# 260115710xxxx-HW-2_0.net
KiCad netlist of a schematic drawn in Altium Designer
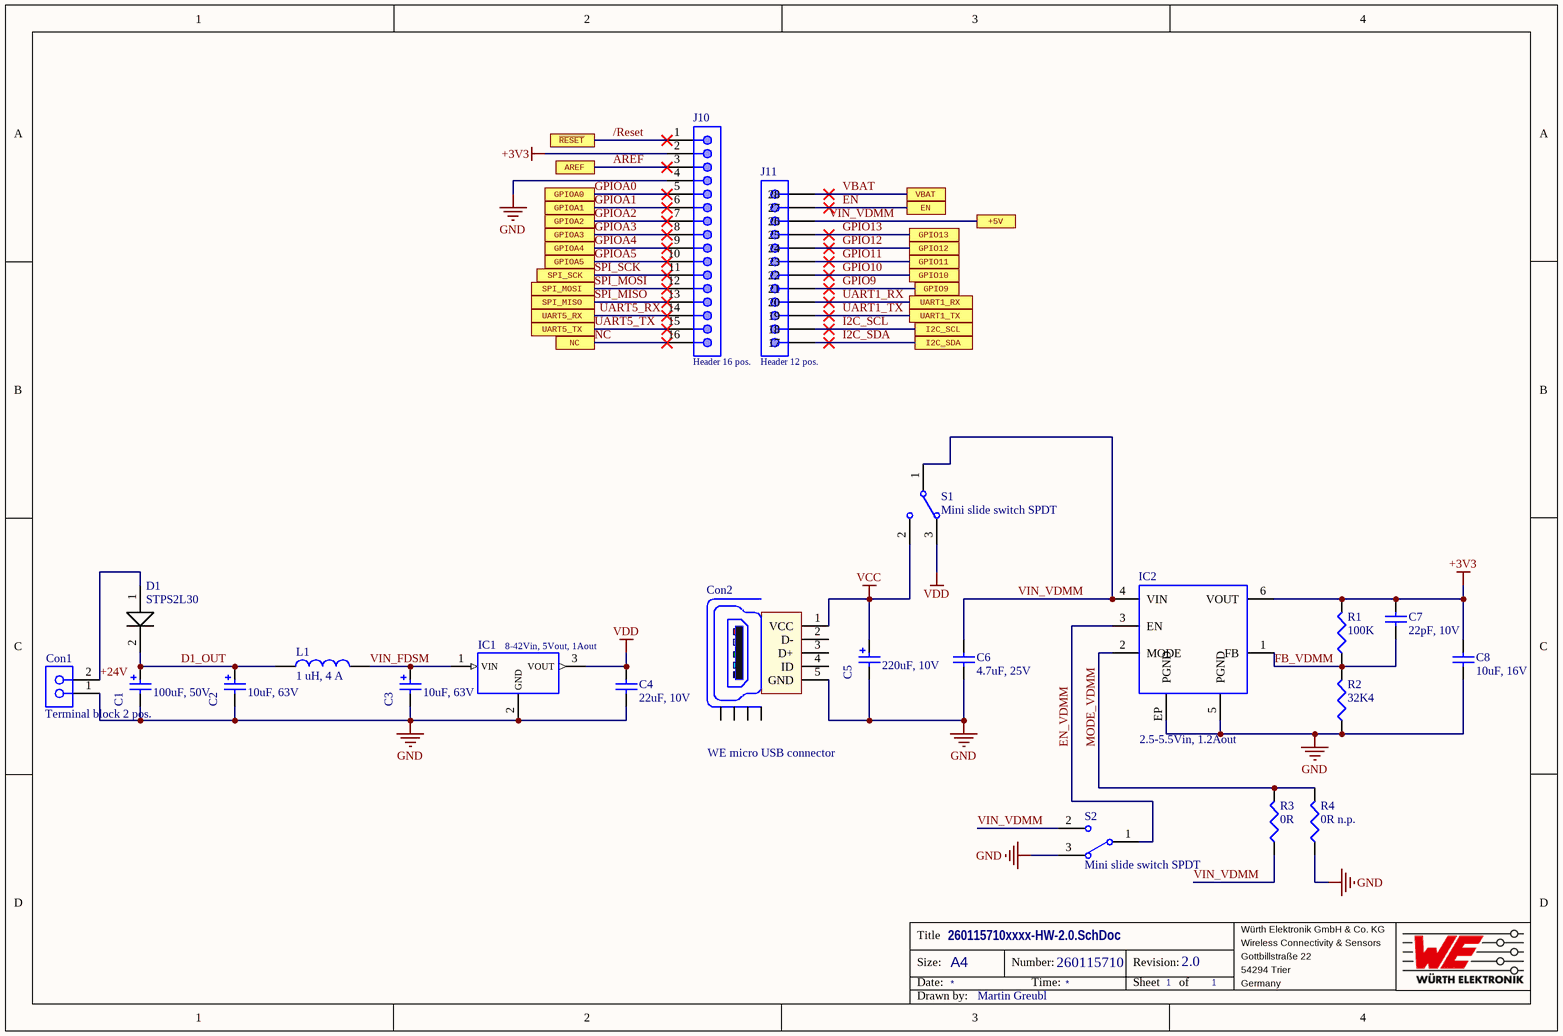
[diagram p0: 260115710xxxx-HW-2.0.SchDoc]

(export (version "E")
  (design (tool "Eeschema 10.0.6"))
  (components
    (comp (ref "C1")
      (value "100uF, 50V")
      (footprint "WCAP-ATG8_8x11.5")
      (description "WCAP-ATG8 THT Aluminum Electrolytic Capacitors, D8mm x L11.5mm, 100uF, +/-20%, 50VDC")
      (fields
        (field (name "PART NUMBER") "860010674014")
        (field (name "MANUFACTURER") "Würth Elektronik eiSos")
        (field (name "PUBLISHER") "Wurth Elektronik")
      )
      (libsource (lib "860010672001_Altium_WCAP-ATG8_rev19a") (part "860010674014"))
    )
    (comp (ref "C2")
      (value "10uF, 63V")
      (footprint "WCAP-PSHP_8x8.7mm")
      (description "WCAP-PSHP Aluminum Polymer Capacitors, size 8x8.7mm, 10uF, +/-20%, 63VDC")
      (fields
        (field (name "PART NUMBER") "875115852001")
        (field (name "MANUFACTURER") "Würth Elektronik eiSos")
        (field (name "PUBLISHER") "Wurth Elektronik")
      )
      (libsource (lib "875115852001_Altium_WCAP-PSHP_rev19a") (part "875115852001"))
    )
    (comp (ref "C3")
      (value "10uF, 63V")
      (footprint "WCAP-PSHP_8x8.7mm")
      (description "WCAP-PSHP Aluminum Polymer Capacitors, size 8x8.7mm, 10uF, +/-20%, 63VDC")
      (fields
        (field (name "PART NUMBER") "875115852001")
        (field (name "MANUFACTURER") "Würth Elektronik eiSos")
        (field (name "PUBLISHER") "Wurth Elektronik")
      )
      (libsource (lib "875115852001_Altium_WCAP-PSHP_rev19a") (part "875115852001"))
    )
    (comp (ref "C4")
      (value "22uF, 10V")
      (footprint "WCAP-CSGP_0805_H=1.25mm")
      (description "WCAP-CSGP General Purpose Ceramic Capacitors, size 0805, 22uF, +/-20%, 10VDC")
      (fields
        (field (name "PART NUMBER") "885012107011")
        (field (name "MANUFACTURER") "Würth Elektronik eiSos")
        (field (name "PUBLISHER") "Wurth Elektronik")
      )
      (libsource (lib "885012107011_Altium_WCAP-CSGP_rev19b") (part "885012107011"))
    )
    (comp (ref "C5")
      (value "220uF, 10V")
      (footprint "WCAP-PSLP_6.3x5.8")
      (description "WCAP-PSLP Aluminum Polymer Capacitors, D6.3mm, L5.8mm, 220uF, +/-20%, 10VDC")
      (fields
        (field (name "PART NUMBER") "875105244013")
        (field (name "MANUFACTURER") "Würth Elektronik eiSos")
        (field (name "PUBLISHER") "Wurth Elektronik")
      )
      (libsource (lib "875105244013_Altium_WCAP-PSLP_rev19a") (part "875105244013"))
    )
    (comp (ref "C6")
      (value "4.7uF, 25V")
      (footprint "WCAP-CSGP_0805_H=1.25mm")
      (description "WCAP-CSGP General Purpose Ceramic Capacitors, size 0805, 4.7uF, +/-20%, 25VDC")
      (fields
        (field (name "PART NUMBER") "885012107018")
        (field (name "MANUFACTURER") "Würth Elektronik eiSos")
        (field (name "PUBLISHER") "Wurth Elektronik")
      )
      (libsource (lib "885012107011_Altium_WCAP-CSGP_rev19b") (part "885012107018"))
    )
    (comp (ref "C7")
      (value "22pF, 10V")
      (footprint "WCAP-CSGP_0805_H=0.6mm_Reflow")
      (description "WCAP-CSGP General Purpose Ceramic Capacitors, size 0805, 22pF, +/-5%, 10VDC")
      (fields
        (field (name "PART NUMBER") "885012007002")
        (field (name "MANUFACTURER") "Würth Elektronik eiSos")
        (field (name "PUBLISHER") "Wurth Elektronik")
      )
      (libsource (lib "885012107011_Altium_WCAP-CSGP_rev19b") (part "885012007002"))
    )
    (comp (ref "C8")
      (value "10uF, 16V")
      (footprint "WCAP-CSGP_0805_H=1.25mm")
      (description "WCAP-CSGP General Purpose Ceramic Capacitors, size 0805, 10uF, +/-20%, 16VDC")
      (fields
        (field (name "PART NUMBER") "885012107014")
        (field (name "MANUFACTURER") "Würth Elektronik eiSos")
        (field (name "PUBLISHER") "Wurth Elektronik")
      )
      (libsource (lib "885012107011_Altium_WCAP-CSGP_rev19b") (part "885012107014"))
    )
    (comp (ref "Con1")
      (value "Terminal block 2 pos.")
      (footprint "691805010302")
      (description "WR-TBL Serie 8050 Horizontal Entry SMT, Screwless, pitch 2.5mm, 2p")
      (fields
        (field (name "PART NUMBER") "691805010302")
        (field (name "MANUFACTURER") "Würth Elektronik eiSos")
        (field (name "PUBLISHER") "Wurth Elektronik")
      )
      (libsource (lib "691502710002_Altium_WR-TBL_rev19a") (part "691805010302"))
    )
    (comp (ref "Con2")
      (value "WE micro USB connector")
      (footprint "629105136821")
      (description "WR-COM Micro USB SMT Type B")
      (fields
        (field (name "MANUFACTURER") "Würth Elektronik eiSos")
        (field (name "PART NUMBER") "629105136821")
        (field (name "CREATED BY") "Karrer Zheng")
      )
      (libsource (lib "629105136821_Altium_629105136821_rev16d") (part "WE-Communication Connectors 629105136821"))
    )
    (comp (ref "D1")
      (value "Diode 30V/1A")
      (footprint "SMA Flat")
      (description "Single chip Schottky rectifiers STPS2L30, size SMA Flat, If 1 A, Vrrm 30 V, Vf 0.325 V")
      (fields
        (field (name "PART NUMBER") "STPS2L30")
        (field (name "MANUFACTURER") "STMicroelectronics")
        (field (name "PUBLISHER") "STMicroelectronics")
      )
      (libsource (lib "Diode") (part "STPS2L30"))
    )
    (comp (ref "IC1")
      (value "8-42Vin, 5Vout, 1Aout")
      (footprint "173010x35")
      (description "MagI3C-FDSM Fixed Step Down Regulator Module, SIP-3, 8-36Vin, 5Vout, 1Aout")
      (fields
        (field (name "PART NUMBER") "173010542")
        (field (name "MANUFACTURER") "Würth Elektronik eiSos")
        (field (name "PUBLISHER") "Wurth Elektronik")
      )
      (libsource (lib "173010335_Altium_MAGIC-FDSM_rev20a") (part "173010535"))
    )
    (comp (ref "IC2")
      (value "2.5-5.5Vin, 1.2Aout")
      (footprint "171010550")
      (description "MagI3C-VDMM Variable Step Down MicroModule, LGA-6EP, 2.5-5.5Vin, 1.2Aout")
      (fields
        (field (name "PART NUMBER") "171010550")
        (field (name "MANUFACTURER") "Würth Elektronik eiSos")
        (field (name "PUBLISHER") "Wurth Elektronik")
      )
      (libsource (lib "171010550_Altium_MAGIC-VDMM_rev19b") (part "171010550"))
    )
    (comp (ref "J10")
      (value "Header 16 pos.")
      (footprint "61301611121")
      (description "THT Vertical Pin Header WR-PHD, Pitch 2.54 mm, Single Row, 16 pins")
      (fields
        (field (name "PART NUMBER") "SSQ-116-03-T-S")
        (field (name "MANUFACTURER") "Samtec")
        (field (name "PUBLISHER") "Samtec")
      )
      (libsource (lib "ALTIUM-PHD_2_54_THT_PIN_HEADER_6130XX11121-rev18b") (part "61301611121"))
    )
    (comp (ref "J11")
      (value "Header 12 pos.")
      (footprint "61301211121")
      (description "THT Vertical Pin Header WR-PHD, Pitch 2.54 mm, Single Row, 12 pins")
      (fields
        (field (name "PART NUMBER") "SSQ-116-03-T-S")
        (field (name "MANUFACTURER") "Samtec")
        (field (name "PUBLISHER") "Samtec")
      )
      (libsource (lib "ALTIUM-PHD_2_54_THT_PIN_HEADER_6130XX11121-rev18b") (part "61301211121"))
    )
    (comp (ref "L1")
      (value "1 uH, 4 A")
      (footprint "WE-PD2_4532")
      (description "SMT Power Inductor WE-PD2, size 4532, 1 uH, 4 A")
      (fields
        (field (name "PART NUMBER") "7447730")
        (field (name "MANUFACTURER") "Würth Elektronik eiSos")
        (field (name "PUBLISHER") "Wurth Elektronik")
      )
      (libsource (lib "744774112_Altium_WE-PD2_rev18b") (part "7447730"))
    )
    (comp (ref "R1")
      (value "100K")
      (footprint "SMD Resistor 0603 IPC")
      (description "SMD Resistor /100k / 0603/ 1%")
      (fields
        (field (name "MANUFACTURER") "Yageo")
        (field (name "PART NUMBER") "AC0603FR-10100KL")
        (field (name "PUBLISHER") "Würth Elektronik")
      )
      (libsource (lib "GAR_Internal") (part "SMD_Resistor"))
    )
    (comp (ref "R2")
      (value "32K4")
      (footprint "SMD Resistor 0603 IPC")
      (description "SMD Resistor / 32k4 / 0603 / 1%")
      (fields
        (field (name "MANUFACTURER") "Yageo")
        (field (name "PART NUMBER") "RC0603FR-0732K4L")
        (field (name "PUBLISHER") "Würth Elektronik")
      )
      (libsource (lib "GAR_Internal") (part "SMD_Resistor"))
    )
    (comp (ref "R3")
      (value "0R")
      (footprint "SMD Resistor 0402 IPC")
      (description "SMD Resistor / 0R / 0402 / 1%")
      (fields
        (field (name "MANUFACTURER") "Yageo")
        (field (name "PART NUMBER") "RC0402FR-070RL")
        (field (name "PUBLISHER") "Würth Elektronik")
      )
      (libsource (lib "GAR_Internal") (part "SMD_Resistor"))
    )
    (comp (ref "R4")
      (value "0R n.p.")
      (footprint "SMD Resistor 0402 IPC")
      (description "SMD Resistor / 0R / 0402 / 1%")
      (fields
        (field (name "MANUFACTURER") "Yageo")
        (field (name "PART NUMBER") "RC0402FR-070RL")
        (field (name "PUBLISHER") "Würth Elektronik")
      )
      (libsource (lib "GAR_Internal") (part "SMD_Resistor"))
    )
    (comp (ref "S1")
      (value "Mini slide switch SPDT")
      (footprint "450301014042")
      (description "WS-SLTV THT Mini Slide Switch, Opposite Side Connection, SPDT")
      (fields
        (field (name "PART NUMBER") "450301014042")
        (field (name "MANUFACTURER") "Würth Elektronik eiSos")
        (field (name "PUBLISHER") "Wurth Elektronik")
      )
      (libsource (lib "450301014042_Altium_WS-SLTV_rev19a") (part "450301014042"))
    )
    (comp (ref "S2")
      (value "Mini slide switch SPDT")
      (footprint "450301014042")
      (description "WS-SLTV THT Mini Slide Switch, Opposite Side Connection, SPDT")
      (fields
        (field (name "PART NUMBER") "450301014042")
        (field (name "MANUFACTURER") "Würth Elektronik eiSos")
        (field (name "PUBLISHER") "Wurth Elektronik")
      )
      (libsource (lib "450301014042_Altium_WS-SLTV_rev19a") (part "450301014042"))
    )
  )
  (nets
    (net (code "1") (name "+3V3") (class "Default")
      (node (ref "C7") (pin "2") (pinfunction "2_2") (pintype "passive"))
      (node (ref "C8") (pin "1") (pinfunction "1_1") (pintype "passive"))
      (node (ref "IC2") (pin "6") (pinfunction "VOUT_6") (pintype "passive"))
      (node (ref "J10") (pin "2") (pinfunction "2_2") (pintype "passive"))
      (node (ref "R1") (pin "2") (pinfunction "2_2") (pintype "passive"))
    )
    (net (code "2") (name "/+24V") (class "Default")
      (node (ref "Con1") (pin "2") (pinfunction "2_2") (pintype "passive"))
      (node (ref "D1") (pin "1") (pinfunction "1_1") (pintype "passive"))
    )
    (net (code "3") (name "/AREF") (class "Default")
      (node (ref "J10") (pin "3") (pinfunction "3_3") (pintype "passive+no_connect"))
    )
    (net (code "4") (name "/D1_OUT") (class "Default")
      (node (ref "C1") (pin "2") (pinfunction "P_2") (pintype "passive"))
      (node (ref "C2") (pin "2") (pinfunction "P_2") (pintype "passive"))
      (node (ref "D1") (pin "2") (pinfunction "2_2") (pintype "passive"))
      (node (ref "L1") (pin "1") (pinfunction "1_1") (pintype "passive"))
    )
    (net (code "5") (name "/EN") (class "Default")
      (node (ref "J11") (pin "11") (pinfunction "27_11") (pintype "passive"))
    )
    (net (code "6") (name "/EN_VDMM") (class "Default")
      (node (ref "IC2") (pin "3") (pinfunction "EN_3") (pintype "passive"))
      (node (ref "S2") (pin "1") (pinfunction "COM_1") (pintype "passive"))
    )
    (net (code "7") (name "/FB_VDMM") (class "Default")
      (node (ref "C7") (pin "1") (pinfunction "1_1") (pintype "passive"))
      (node (ref "IC2") (pin "1") (pinfunction "FB_1") (pintype "passive"))
      (node (ref "R1") (pin "1") (pinfunction "1_1") (pintype "passive"))
      (node (ref "R2") (pin "2") (pinfunction "2_2") (pintype "passive"))
    )
    (net (code "8") (name "/GPIO9") (class "Default")
      (node (ref "J11") (pin "5") (pinfunction "21_5") (pintype "passive"))
    )
    (net (code "9") (name "/GPIO10") (class "Default")
      (node (ref "J11") (pin "6") (pinfunction "22_6") (pintype "passive"))
    )
    (net (code "10") (name "/GPIO11") (class "Default")
      (node (ref "J11") (pin "7") (pinfunction "23_7") (pintype "passive"))
    )
    (net (code "11") (name "/GPIO12") (class "Default")
      (node (ref "J11") (pin "8") (pinfunction "24_8") (pintype "passive"))
    )
    (net (code "12") (name "/GPIO13") (class "Default")
      (node (ref "J11") (pin "9") (pinfunction "25_9") (pintype "passive"))
    )
    (net (code "13") (name "/GPIOA0") (class "Default")
      (node (ref "J10") (pin "5") (pinfunction "5_5") (pintype "passive+no_connect"))
    )
    (net (code "14") (name "/GPIOA1") (class "Default")
      (node (ref "J10") (pin "6") (pinfunction "6_6") (pintype "passive+no_connect"))
    )
    (net (code "15") (name "/GPIOA2") (class "Default")
      (node (ref "J10") (pin "7") (pinfunction "7_7") (pintype "passive+no_connect"))
    )
    (net (code "16") (name "/GPIOA3") (class "Default")
      (node (ref "J10") (pin "8") (pinfunction "8_8") (pintype "passive+no_connect"))
    )
    (net (code "17") (name "/GPIOA4") (class "Default")
      (node (ref "J10") (pin "9") (pinfunction "9_9") (pintype "passive+no_connect"))
    )
    (net (code "18") (name "/GPIOA5") (class "Default")
      (node (ref "J10") (pin "10") (pinfunction "10_10") (pintype "passive+no_connect"))
    )
    (net (code "19") (name "/I2C_SCL") (class "Default")
      (node (ref "J11") (pin "2") (pinfunction "18_2") (pintype "passive"))
    )
    (net (code "20") (name "/I2C_SDA") (class "Default")
      (node (ref "J11") (pin "1") (pinfunction "17_1") (pintype "passive"))
    )
    (net (code "21") (name "/MODE_VDMM") (class "Default")
      (node (ref "IC2") (pin "2") (pinfunction "MODE_2") (pintype "passive"))
      (node (ref "R3") (pin "2") (pinfunction "2_2") (pintype "passive"))
      (node (ref "R4") (pin "2") (pinfunction "2_2") (pintype "passive"))
    )
    (net (code "22") (name "/NC") (class "Default")
      (node (ref "J10") (pin "16") (pinfunction "16_16") (pintype "passive+no_connect"))
    )
    (net (code "23") (name "/SPI_MISO") (class "Default")
      (node (ref "J10") (pin "13") (pinfunction "13_13") (pintype "passive+no_connect"))
    )
    (net (code "24") (name "/SPI_MOSI") (class "Default")
      (node (ref "J10") (pin "12") (pinfunction "12_12") (pintype "passive+no_connect"))
    )
    (net (code "25") (name "/SPI_SCK") (class "Default")
      (node (ref "J10") (pin "11") (pinfunction "11_11") (pintype "passive+no_connect"))
    )
    (net (code "26") (name "/UART1_RX") (class "Default")
      (node (ref "J11") (pin "4") (pinfunction "20_4") (pintype "passive"))
    )
    (net (code "27") (name "/UART1_TX") (class "Default")
      (node (ref "J11") (pin "3") (pinfunction "19_3") (pintype "passive"))
    )
    (net (code "28") (name "/UART5_RX") (class "Default")
      (node (ref "J10") (pin "14") (pinfunction "14_14") (pintype "passive+no_connect"))
    )
    (net (code "29") (name "/UART5_TX") (class "Default")
      (node (ref "J10") (pin "15") (pinfunction "15_15") (pintype "passive+no_connect"))
    )
    (net (code "30") (name "/VBAT") (class "Default")
      (node (ref "J11") (pin "12") (pinfunction "28_12") (pintype "passive"))
    )
    (net (code "31") (name "/VIN_FDSM") (class "Default")
      (node (ref "C3") (pin "2") (pinfunction "P_2") (pintype "passive"))
      (node (ref "IC1") (pin "1") (pinfunction "VIN_1") (pintype "input"))
      (node (ref "L1") (pin "2") (pinfunction "2_2") (pintype "passive"))
    )
    (net (code "32") (name "/VIN_VDMM") (class "Default")
      (node (ref "C6") (pin "1") (pinfunction "1_1") (pintype "passive"))
      (node (ref "IC2") (pin "4") (pinfunction "VIN_4") (pintype "passive"))
      (node (ref "J11") (pin "10") (pinfunction "26_10") (pintype "passive"))
      (node (ref "R3") (pin "1") (pinfunction "1_1") (pintype "passive"))
      (node (ref "S1") (pin "1") (pinfunction "COM_1") (pintype "passive"))
      (node (ref "S2") (pin "2") (pinfunction "2_2") (pintype "passive"))
    )
    (net (code "33") (name "/{slash}Reset") (class "Default")
      (node (ref "J10") (pin "1") (pinfunction "1_1") (pintype "passive+no_connect"))
    )
    (net (code "34") (name "GND") (class "Default")
      (node (ref "C1") (pin "1") (pinfunction "N_1") (pintype "passive"))
      (node (ref "C2") (pin "1") (pinfunction "N_1") (pintype "passive"))
      (node (ref "C3") (pin "1") (pinfunction "N_1") (pintype "passive"))
      (node (ref "C4") (pin "2") (pinfunction "2_2") (pintype "passive"))
      (node (ref "C5") (pin "1") (pinfunction "N_1") (pintype "passive"))
      (node (ref "C6") (pin "2") (pinfunction "2_2") (pintype "passive"))
      (node (ref "C8") (pin "2") (pinfunction "2_2") (pintype "passive"))
      (node (ref "Con1") (pin "1") (pinfunction "1_1") (pintype "passive"))
      (node (ref "Con2") (pin "5") (pinfunction "GND_5") (pintype "passive"))
      (node (ref "IC1") (pin "2") (pinfunction "GND_2") (pintype "passive"))
      (node (ref "IC2") (pin "5") (pinfunction "PGND_5") (pintype "passive"))
      (node (ref "IC2") (pin "EP") (pinfunction "PGND_EP") (pintype "passive"))
      (node (ref "J10") (pin "4") (pinfunction "4_4") (pintype "passive"))
      (node (ref "R2") (pin "1") (pinfunction "1_1") (pintype "passive"))
      (node (ref "R4") (pin "1") (pinfunction "1_1") (pintype "passive"))
      (node (ref "S2") (pin "3") (pinfunction "3_3") (pintype "passive"))
    )
    (net (code "35") (name "VCC") (class "Default")
      (node (ref "C5") (pin "2") (pinfunction "P_2") (pintype "passive"))
      (node (ref "Con2") (pin "1") (pinfunction "VCC_1") (pintype "passive"))
      (node (ref "S1") (pin "2") (pinfunction "2_2") (pintype "passive"))
    )
    (net (code "36") (name "VDD") (class "Default")
      (node (ref "C4") (pin "1") (pinfunction "1_1") (pintype "passive"))
      (node (ref "IC1") (pin "3") (pinfunction "VOUT_3") (pintype "output"))
      (node (ref "S1") (pin "3") (pinfunction "3_3") (pintype "passive"))
    )
    (net (code "37") (name "unconnected-(Con2-D+-Pad3)") (class "Default")
      (node (ref "Con2") (pin "3") (pinfunction "D+_3") (pintype "passive"))
    )
    (net (code "38") (name "unconnected-(Con2-D--Pad2)") (class "Default")
      (node (ref "Con2") (pin "2") (pinfunction "D-_2") (pintype "passive"))
    )
    (net (code "39") (name "unconnected-(Con2-ID-Pad4)") (class "Default")
      (node (ref "Con2") (pin "4") (pinfunction "ID_4") (pintype "passive"))
    )
    (net (code "40") (name "unconnected-(Con2-Shield-PadZ1)") (class "Default")
      (node (ref "Con2") (pin "Z1") (pinfunction "Shield_Z1") (pintype "passive"))
    )
    (net (code "41") (name "unconnected-(Con2-Shield-PadZ2)") (class "Default")
      (node (ref "Con2") (pin "Z2") (pinfunction "Shield_Z2") (pintype "passive"))
    )
    (net (code "42") (name "unconnected-(Con2-Shield-PadZ3)") (class "Default")
      (node (ref "Con2") (pin "Z3") (pinfunction "Shield_Z3") (pintype "passive"))
    )
    (net (code "43") (name "unconnected-(Con2-Shield-PadZ4)") (class "Default")
      (node (ref "Con2") (pin "Z4") (pinfunction "Shield_Z4") (pintype "passive"))
    )
  )
)
